# mega_meco.net
KiCad netlist of a schematic drawn in EAGLE
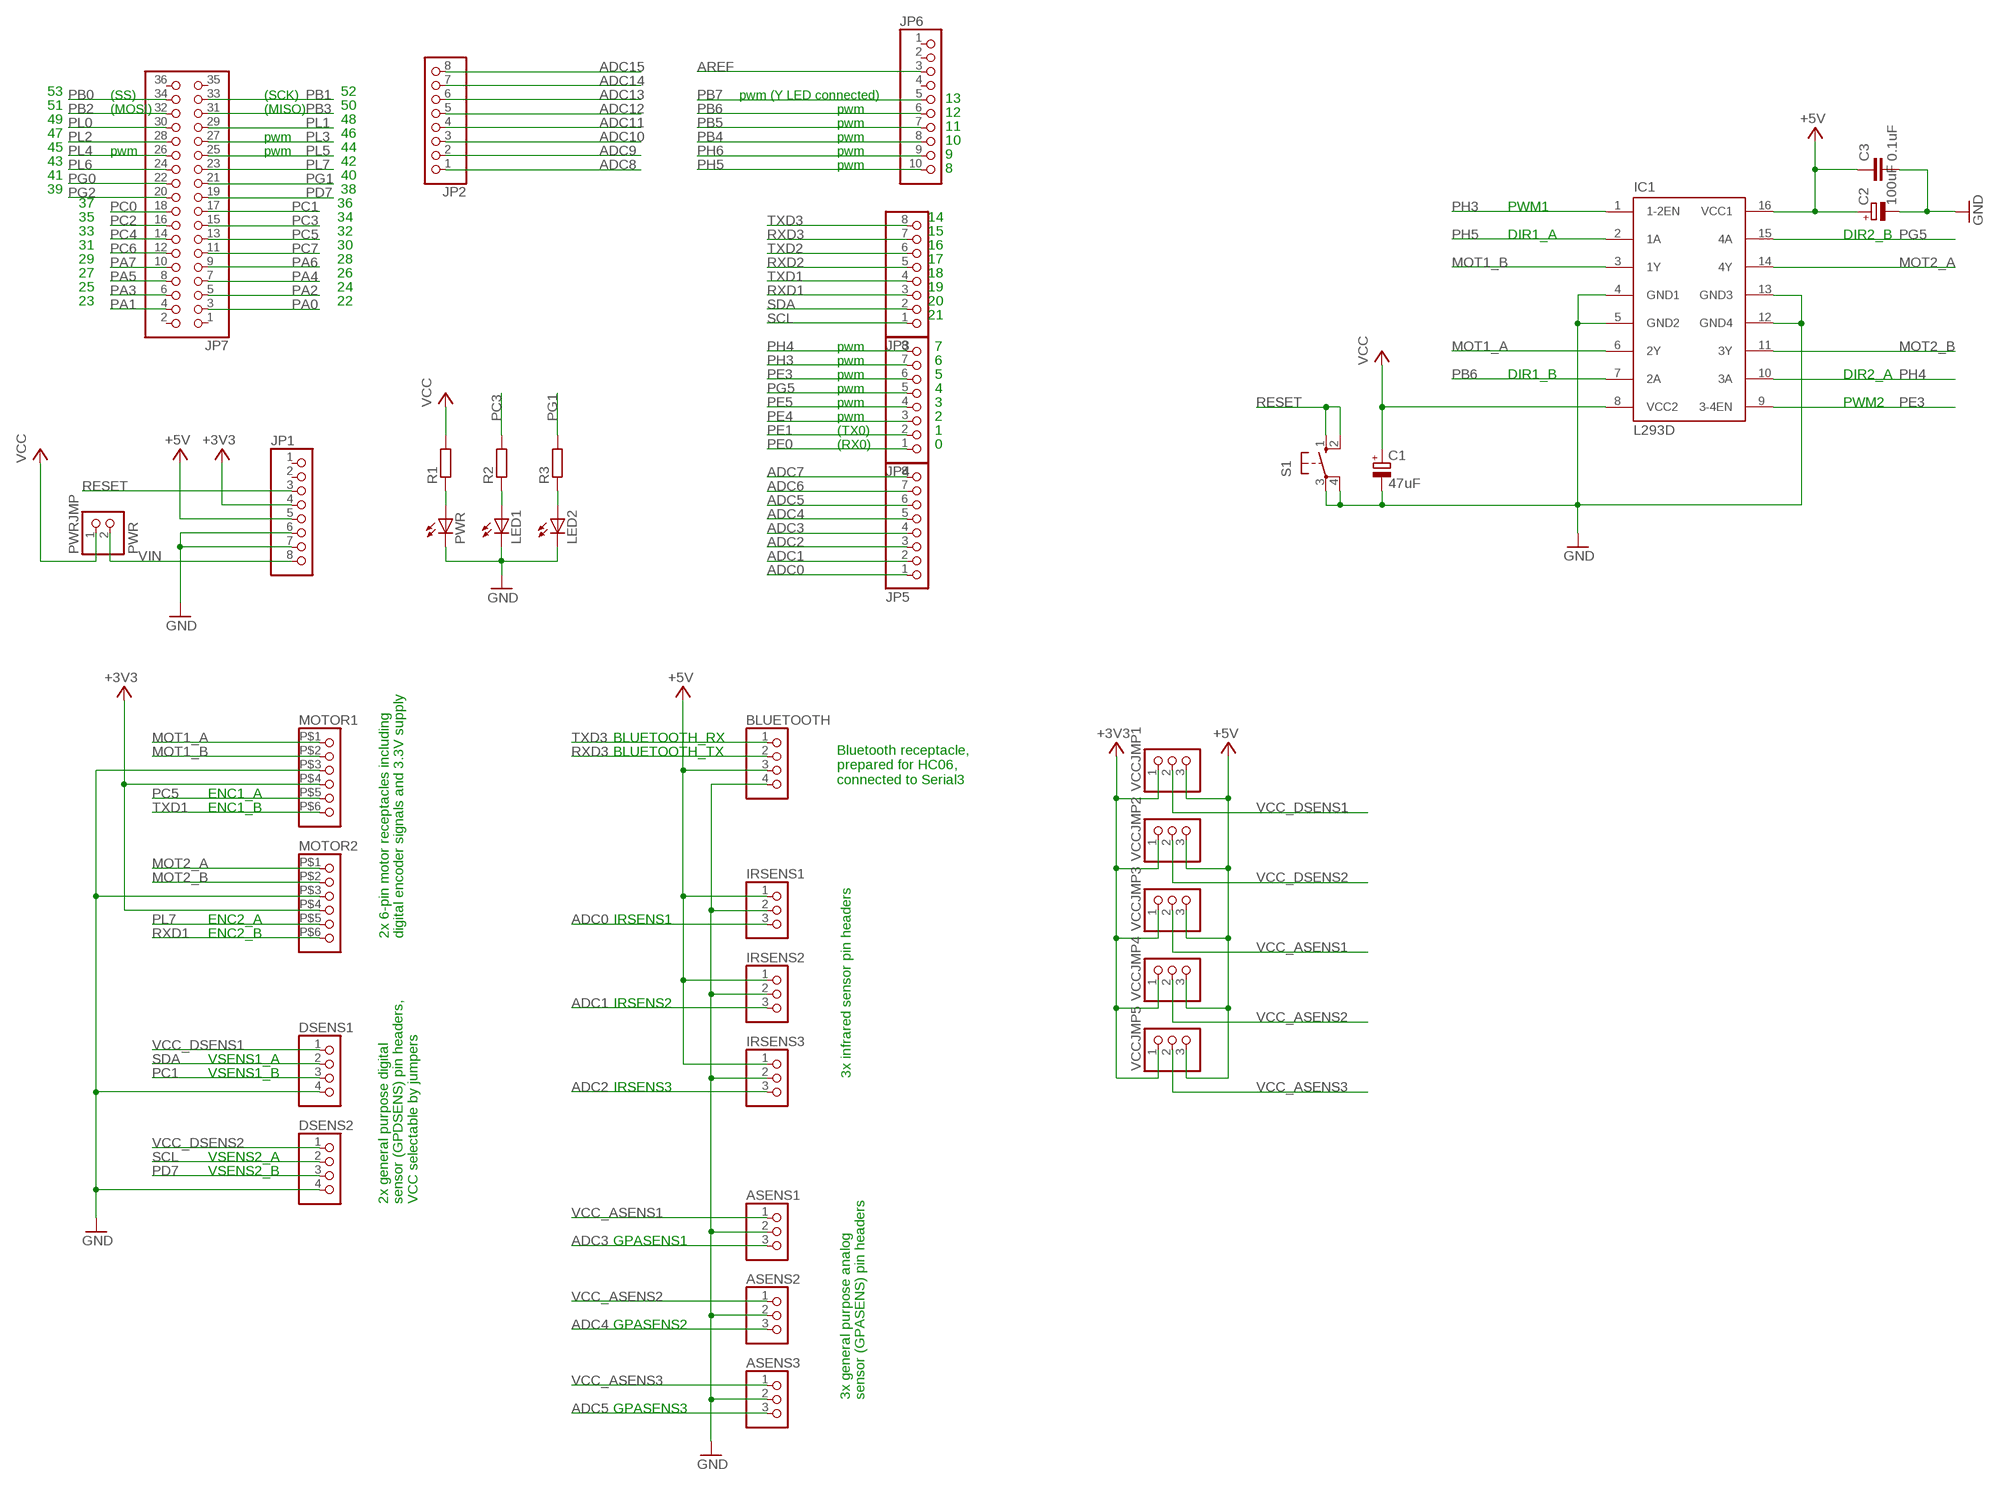
[diagram p0: schematic, sheet 1]

(export (version "E")
  (design (tool "Eeschema 10.0.6"))
  (components
    (comp (ref "ASENS1")
      (value "PINHD-1X3")
      (footprint "eagle-import:1X03")
      (libsource (lib "eagle-import") (part "PINHD-1X3"))
    )
    (comp (ref "ASENS2")
      (value "PINHD-1X3")
      (footprint "eagle-import:1X03")
      (libsource (lib "eagle-import") (part "PINHD-1X3"))
    )
    (comp (ref "ASENS3")
      (value "PINHD-1X3")
      (footprint "eagle-import:1X03")
      (libsource (lib "eagle-import") (part "PINHD-1X3"))
    )
    (comp (ref "BLUETOOTH")
      (value "PINHD-1X4")
      (footprint "eagle-import:1X04")
      (libsource (lib "eagle-import") (part "PINHD-1X4"))
    )
    (comp (ref "C1")
      (value "47uF")
      (footprint "eagle-import:E2-5")
      (libsource (lib "eagle-import") (part "CPOL-EUE2-5"))
    )
    (comp (ref "C2")
      (value "100uF")
      (footprint "eagle-import:E2-5")
      (libsource (lib "eagle-import") (part "CPOL-EUE2-5"))
    )
    (comp (ref "C3")
      (value "0.1uF")
      (footprint "eagle-import:C025-025X050")
      (libsource (lib "eagle-import") (part "C-EU025-025X050"))
    )
    (comp (ref "DSENS1")
      (value "PINHD-1X4")
      (footprint "eagle-import:1X04")
      (libsource (lib "eagle-import") (part "PINHD-1X4"))
    )
    (comp (ref "DSENS2")
      (value "PINHD-1X4")
      (footprint "eagle-import:1X04")
      (libsource (lib "eagle-import") (part "PINHD-1X4"))
    )
    (comp (ref "IC1")
      (value "L293D")
      (footprint "eagle-import:DIL16")
      (fields (field (name "MF") "Arrow Electronics") (field (name "MPN") "L293E"))
      (libsource (lib "eagle-import") (part "L293E"))
    )
    (comp (ref "IRSENS1")
      (value "PINHD-1X3")
      (footprint "eagle-import:1X03")
      (libsource (lib "eagle-import") (part "PINHD-1X3"))
    )
    (comp (ref "IRSENS2")
      (value "PINHD-1X3")
      (footprint "eagle-import:1X03")
      (libsource (lib "eagle-import") (part "PINHD-1X3"))
    )
    (comp (ref "IRSENS3")
      (value "PINHD-1X3")
      (footprint "eagle-import:1X03")
      (libsource (lib "eagle-import") (part "PINHD-1X3"))
    )
    (comp (ref "JP1")
      (value "PINHD-1X8")
      (footprint "eagle-import:1X08")
      (libsource (lib "eagle-import") (part "PINHD-1X8"))
    )
    (comp (ref "JP2")
      (value "PINHD-1X8")
      (footprint "eagle-import:1X08")
      (libsource (lib "eagle-import") (part "PINHD-1X8"))
    )
    (comp (ref "JP3")
      (value "PINHD-1X8")
      (footprint "eagle-import:1X08")
      (libsource (lib "eagle-import") (part "PINHD-1X8"))
    )
    (comp (ref "JP4")
      (value "PINHD-1X8")
      (footprint "eagle-import:1X08")
      (libsource (lib "eagle-import") (part "PINHD-1X8"))
    )
    (comp (ref "JP5")
      (value "PINHD-1X8")
      (footprint "eagle-import:1X08")
      (libsource (lib "eagle-import") (part "PINHD-1X8"))
    )
    (comp (ref "JP6")
      (value "PINHD-1X10")
      (footprint "eagle-import:1X10")
      (libsource (lib "eagle-import") (part "PINHD-1X10"))
    )
    (comp (ref "JP7")
      (value "PINHD-2X18")
      (footprint "eagle-import:2X18")
      (libsource (lib "eagle-import") (part "PINHD-2X18"))
    )
    (comp (ref "LED1")
      (value "LED3MM")
      (footprint "eagle-import:LED3MM")
      (libsource (lib "eagle-import") (part "LED3MM"))
    )
    (comp (ref "LED2")
      (value "LED3MM")
      (footprint "eagle-import:LED3MM")
      (libsource (lib "eagle-import") (part "LED3MM"))
    )
    (comp (ref "MOTOR1")
      (value "PINHD-1X6-2.5MM")
      (footprint "eagle-import:1X06-2.5MM")
      (libsource (lib "eagle-import") (part "PINHD-1X6-2.5MM"))
    )
    (comp (ref "MOTOR2")
      (value "PINHD-1X6-2.5MM")
      (footprint "eagle-import:1X06-2.5MM")
      (libsource (lib "eagle-import") (part "PINHD-1X6-2.5MM"))
    )
    (comp (ref "PWR")
      (value "LED5MM")
      (footprint "eagle-import:LED5MM")
      (libsource (lib "eagle-import") (part "LED5MM"))
    )
    (comp (ref "PWRJMP")
      (value "PWR")
      (footprint "eagle-import:1X02")
      (libsource (lib "eagle-import") (part "PINHD-1X2"))
    )
    (comp (ref "R1")
      (value "R-EU_0204/5")
      (footprint "eagle-import:0204_5")
      (libsource (lib "eagle-import") (part "R-EU_0204/5"))
    )
    (comp (ref "R2")
      (value "R-EU_0204/5")
      (footprint "eagle-import:0204_5")
      (libsource (lib "eagle-import") (part "R-EU_0204/5"))
    )
    (comp (ref "R3")
      (value "R-EU_0204/5")
      (footprint "eagle-import:0204_5")
      (libsource (lib "eagle-import") (part "R-EU_0204/5"))
    )
    (comp (ref "S1")
      (value "10-XX")
      (footprint "eagle-import:B3F-10XX")
      (fields (field (name "MPN") "B3F-1000"))
      (libsource (lib "eagle-import") (part "10-XX"))
    )
    (comp (ref "VCCJMP1")
      (value "PINHD-1X3")
      (footprint "eagle-import:1X03")
      (libsource (lib "eagle-import") (part "PINHD-1X3"))
    )
    (comp (ref "VCCJMP2")
      (value "PINHD-1X3")
      (footprint "eagle-import:1X03")
      (libsource (lib "eagle-import") (part "PINHD-1X3"))
    )
    (comp (ref "VCCJMP3")
      (value "PINHD-1X3")
      (footprint "eagle-import:1X03")
      (libsource (lib "eagle-import") (part "PINHD-1X3"))
    )
    (comp (ref "VCCJMP4")
      (value "PINHD-1X3")
      (footprint "eagle-import:1X03")
      (libsource (lib "eagle-import") (part "PINHD-1X3"))
    )
    (comp (ref "VCCJMP5")
      (value "PINHD-1X3")
      (footprint "eagle-import:1X03")
      (libsource (lib "eagle-import") (part "PINHD-1X3"))
    )
  )
  (nets
    (net (code "1") (name "+3V3") (class "Default")
      (node (ref "JP1") (pin "4") (pinfunction "4_4") (pintype "passive"))
      (node (ref "MOTOR1") (pin "P$4") (pinfunction "4_P$4") (pintype "passive"))
      (node (ref "MOTOR2") (pin "P$4") (pinfunction "4_P$4") (pintype "passive"))
      (node (ref "VCCJMP1") (pin "1") (pinfunction "1_1") (pintype "passive"))
      (node (ref "VCCJMP2") (pin "1") (pinfunction "1_1") (pintype "passive"))
      (node (ref "VCCJMP3") (pin "1") (pinfunction "1_1") (pintype "passive"))
      (node (ref "VCCJMP4") (pin "1") (pinfunction "1_1") (pintype "passive"))
      (node (ref "VCCJMP5") (pin "1") (pinfunction "1_1") (pintype "passive"))
    )
    (net (code "2") (name "+5V") (class "Default")
      (node (ref "BLUETOOTH") (pin "3") (pinfunction "3_3") (pintype "passive"))
      (node (ref "C2") (pin "+") (pinfunction "+_+") (pintype "passive"))
      (node (ref "C3") (pin "1") (pinfunction "1_1") (pintype "passive"))
      (node (ref "IC1") (pin "16") (pinfunction "VCC1_16") (pintype "power_in"))
      (node (ref "IRSENS1") (pin "1") (pinfunction "1_1") (pintype "passive"))
      (node (ref "IRSENS2") (pin "1") (pinfunction "1_1") (pintype "passive"))
      (node (ref "IRSENS3") (pin "1") (pinfunction "1_1") (pintype "passive"))
      (node (ref "JP1") (pin "5") (pinfunction "5_5") (pintype "passive"))
      (node (ref "VCCJMP1") (pin "3") (pinfunction "3_3") (pintype "passive"))
      (node (ref "VCCJMP2") (pin "3") (pinfunction "3_3") (pintype "passive"))
      (node (ref "VCCJMP3") (pin "3") (pinfunction "3_3") (pintype "passive"))
      (node (ref "VCCJMP4") (pin "3") (pinfunction "3_3") (pintype "passive"))
      (node (ref "VCCJMP5") (pin "3") (pinfunction "3_3") (pintype "passive"))
    )
    (net (code "3") (name "/ADC0") (class "Default")
      (node (ref "IRSENS1") (pin "3") (pinfunction "3_3") (pintype "passive"))
      (node (ref "JP5") (pin "1") (pinfunction "1_1") (pintype "passive"))
    )
    (net (code "4") (name "/ADC1") (class "Default")
      (node (ref "IRSENS2") (pin "3") (pinfunction "3_3") (pintype "passive"))
      (node (ref "JP5") (pin "2") (pinfunction "2_2") (pintype "passive"))
    )
    (net (code "5") (name "/ADC2") (class "Default")
      (node (ref "IRSENS3") (pin "3") (pinfunction "3_3") (pintype "passive"))
      (node (ref "JP5") (pin "3") (pinfunction "3_3") (pintype "passive"))
    )
    (net (code "6") (name "/ADC3") (class "Default")
      (node (ref "ASENS1") (pin "3") (pinfunction "3_3") (pintype "passive"))
      (node (ref "JP5") (pin "4") (pinfunction "4_4") (pintype "passive"))
    )
    (net (code "7") (name "/ADC4") (class "Default")
      (node (ref "ASENS2") (pin "3") (pinfunction "3_3") (pintype "passive"))
      (node (ref "JP5") (pin "5") (pinfunction "5_5") (pintype "passive"))
    )
    (net (code "8") (name "/ADC5") (class "Default")
      (node (ref "ASENS3") (pin "3") (pinfunction "3_3") (pintype "passive"))
      (node (ref "JP5") (pin "6") (pinfunction "6_6") (pintype "passive"))
    )
    (net (code "9") (name "/ADC6") (class "Default")
      (node (ref "JP5") (pin "7") (pinfunction "7_7") (pintype "passive"))
    )
    (net (code "10") (name "/ADC7") (class "Default")
      (node (ref "JP5") (pin "8") (pinfunction "8_8") (pintype "passive"))
    )
    (net (code "11") (name "/ADC8") (class "Default")
      (node (ref "JP2") (pin "1") (pinfunction "1_1") (pintype "passive"))
    )
    (net (code "12") (name "/ADC9") (class "Default")
      (node (ref "JP2") (pin "2") (pinfunction "2_2") (pintype "passive"))
    )
    (net (code "13") (name "/ADC10") (class "Default")
      (node (ref "JP2") (pin "3") (pinfunction "3_3") (pintype "passive"))
    )
    (net (code "14") (name "/ADC11") (class "Default")
      (node (ref "JP2") (pin "4") (pinfunction "4_4") (pintype "passive"))
    )
    (net (code "15") (name "/ADC12") (class "Default")
      (node (ref "JP2") (pin "5") (pinfunction "5_5") (pintype "passive"))
    )
    (net (code "16") (name "/ADC13") (class "Default")
      (node (ref "JP2") (pin "6") (pinfunction "6_6") (pintype "passive"))
    )
    (net (code "17") (name "/ADC14") (class "Default")
      (node (ref "JP2") (pin "7") (pinfunction "7_7") (pintype "passive"))
    )
    (net (code "18") (name "/ADC15") (class "Default")
      (node (ref "JP2") (pin "8") (pinfunction "8_8") (pintype "passive"))
    )
    (net (code "19") (name "/AREF") (class "Default")
      (node (ref "JP6") (pin "3") (pinfunction "3_3") (pintype "passive"))
    )
    (net (code "20") (name "/MOT1_A") (class "Default")
      (node (ref "IC1") (pin "6") (pinfunction "2Y_6") (pintype "output"))
      (node (ref "MOTOR1") (pin "P$1") (pinfunction "1_P$1") (pintype "passive"))
    )
    (net (code "21") (name "/MOT1_B") (class "Default")
      (node (ref "IC1") (pin "3") (pinfunction "1Y_3") (pintype "output"))
      (node (ref "MOTOR1") (pin "P$2") (pinfunction "2_P$2") (pintype "passive"))
    )
    (net (code "22") (name "/MOT2_A") (class "Default")
      (node (ref "IC1") (pin "14") (pinfunction "4Y_14") (pintype "output"))
      (node (ref "MOTOR2") (pin "P$1") (pinfunction "1_P$1") (pintype "passive"))
    )
    (net (code "23") (name "/MOT2_B") (class "Default")
      (node (ref "IC1") (pin "11") (pinfunction "3Y_11") (pintype "output"))
      (node (ref "MOTOR2") (pin "P$2") (pinfunction "2_P$2") (pintype "passive"))
    )
    (net (code "24") (name "/PA0") (class "Default")
      (node (ref "JP7") (pin "3") (pinfunction "3_3") (pintype "passive"))
    )
    (net (code "25") (name "/PA1") (class "Default")
      (node (ref "JP7") (pin "4") (pinfunction "4_4") (pintype "passive"))
    )
    (net (code "26") (name "/PA2") (class "Default")
      (node (ref "JP7") (pin "5") (pinfunction "5_5") (pintype "passive"))
    )
    (net (code "27") (name "/PA3") (class "Default")
      (node (ref "JP7") (pin "6") (pinfunction "6_6") (pintype "passive"))
    )
    (net (code "28") (name "/PA4") (class "Default")
      (node (ref "JP7") (pin "7") (pinfunction "7_7") (pintype "passive"))
    )
    (net (code "29") (name "/PA5") (class "Default")
      (node (ref "JP7") (pin "8") (pinfunction "8_8") (pintype "passive"))
    )
    (net (code "30") (name "/PA6") (class "Default")
      (node (ref "JP7") (pin "9") (pinfunction "9_9") (pintype "passive"))
    )
    (net (code "31") (name "/PA7") (class "Default")
      (node (ref "JP7") (pin "10") (pinfunction "10_10") (pintype "passive"))
    )
    (net (code "32") (name "/PB0") (class "Default")
      (node (ref "JP7") (pin "34") (pinfunction "34_34") (pintype "passive"))
    )
    (net (code "33") (name "/PB1") (class "Default")
      (node (ref "JP7") (pin "33") (pinfunction "33_33") (pintype "passive"))
    )
    (net (code "34") (name "/PB2") (class "Default")
      (node (ref "JP7") (pin "32") (pinfunction "32_32") (pintype "passive"))
    )
    (net (code "35") (name "/PB3") (class "Default")
      (node (ref "JP7") (pin "31") (pinfunction "31_31") (pintype "passive"))
    )
    (net (code "36") (name "/PB4") (class "Default")
      (node (ref "JP6") (pin "8") (pinfunction "8_8") (pintype "passive"))
    )
    (net (code "37") (name "/PB5") (class "Default")
      (node (ref "JP6") (pin "7") (pinfunction "7_7") (pintype "passive"))
    )
    (net (code "38") (name "/PB6") (class "Default")
      (node (ref "IC1") (pin "7") (pinfunction "2A_7") (pintype "input"))
      (node (ref "JP6") (pin "6") (pinfunction "6_6") (pintype "passive"))
    )
    (net (code "39") (name "/PB7") (class "Default")
      (node (ref "JP6") (pin "5") (pinfunction "5_5") (pintype "passive"))
    )
    (net (code "40") (name "/PC0") (class "Default")
      (node (ref "JP7") (pin "18") (pinfunction "18_18") (pintype "passive"))
    )
    (net (code "41") (name "/PC1") (class "Default")
      (node (ref "DSENS1") (pin "3") (pinfunction "3_3") (pintype "passive"))
      (node (ref "JP7") (pin "17") (pinfunction "17_17") (pintype "passive"))
    )
    (net (code "42") (name "/PC2") (class "Default")
      (node (ref "JP7") (pin "16") (pinfunction "16_16") (pintype "passive"))
    )
    (net (code "43") (name "/PC3") (class "Default")
      (node (ref "JP7") (pin "15") (pinfunction "15_15") (pintype "passive"))
      (node (ref "R2") (pin "2") (pinfunction "2_2") (pintype "passive"))
    )
    (net (code "44") (name "/PC4") (class "Default")
      (node (ref "JP7") (pin "14") (pinfunction "14_14") (pintype "passive"))
    )
    (net (code "45") (name "/PC5") (class "Default")
      (node (ref "JP7") (pin "13") (pinfunction "13_13") (pintype "passive"))
      (node (ref "MOTOR1") (pin "P$5") (pinfunction "5_P$5") (pintype "passive"))
    )
    (net (code "46") (name "/PC6") (class "Default")
      (node (ref "JP7") (pin "12") (pinfunction "12_12") (pintype "passive"))
    )
    (net (code "47") (name "/PC7") (class "Default")
      (node (ref "JP7") (pin "11") (pinfunction "11_11") (pintype "passive"))
    )
    (net (code "48") (name "/PD7") (class "Default")
      (node (ref "DSENS2") (pin "3") (pinfunction "3_3") (pintype "passive"))
      (node (ref "JP7") (pin "19") (pinfunction "19_19") (pintype "passive"))
    )
    (net (code "49") (name "/PE0") (class "Default")
      (node (ref "JP4") (pin "1") (pinfunction "1_1") (pintype "passive"))
    )
    (net (code "50") (name "/PE1") (class "Default")
      (node (ref "JP4") (pin "2") (pinfunction "2_2") (pintype "passive"))
    )
    (net (code "51") (name "/PE3") (class "Default")
      (node (ref "IC1") (pin "9") (pinfunction "3-4EN_9") (pintype "input"))
      (node (ref "JP4") (pin "6") (pinfunction "6_6") (pintype "passive"))
    )
    (net (code "52") (name "/PE4") (class "Default")
      (node (ref "JP4") (pin "3") (pinfunction "3_3") (pintype "passive"))
    )
    (net (code "53") (name "/PE5") (class "Default")
      (node (ref "JP4") (pin "4") (pinfunction "4_4") (pintype "passive"))
    )
    (net (code "54") (name "/PG0") (class "Default")
      (node (ref "JP7") (pin "22") (pinfunction "22_22") (pintype "passive"))
    )
    (net (code "55") (name "/PG1") (class "Default")
      (node (ref "JP7") (pin "21") (pinfunction "21_21") (pintype "passive"))
      (node (ref "R3") (pin "2") (pinfunction "2_2") (pintype "passive"))
    )
    (net (code "56") (name "/PG2") (class "Default")
      (node (ref "JP7") (pin "20") (pinfunction "20_20") (pintype "passive"))
    )
    (net (code "57") (name "/PG5") (class "Default")
      (node (ref "IC1") (pin "15") (pinfunction "4A_15") (pintype "input"))
      (node (ref "JP4") (pin "5") (pinfunction "5_5") (pintype "passive"))
    )
    (net (code "58") (name "/PH3") (class "Default")
      (node (ref "IC1") (pin "1") (pinfunction "1-2EN_1") (pintype "input"))
      (node (ref "JP4") (pin "7") (pinfunction "7_7") (pintype "passive"))
    )
    (net (code "59") (name "/PH4") (class "Default")
      (node (ref "IC1") (pin "10") (pinfunction "3A_10") (pintype "input"))
      (node (ref "JP4") (pin "8") (pinfunction "8_8") (pintype "passive"))
    )
    (net (code "60") (name "/PH5") (class "Default")
      (node (ref "IC1") (pin "2") (pinfunction "1A_2") (pintype "input"))
      (node (ref "JP6") (pin "10") (pinfunction "10_10") (pintype "passive"))
    )
    (net (code "61") (name "/PH6") (class "Default")
      (node (ref "JP6") (pin "9") (pinfunction "9_9") (pintype "passive"))
    )
    (net (code "62") (name "/PL0") (class "Default")
      (node (ref "JP7") (pin "30") (pinfunction "30_30") (pintype "passive"))
    )
    (net (code "63") (name "/PL1") (class "Default")
      (node (ref "JP7") (pin "29") (pinfunction "29_29") (pintype "passive"))
    )
    (net (code "64") (name "/PL2") (class "Default")
      (node (ref "JP7") (pin "28") (pinfunction "28_28") (pintype "passive"))
    )
    (net (code "65") (name "/PL3") (class "Default")
      (node (ref "JP7") (pin "27") (pinfunction "27_27") (pintype "passive"))
    )
    (net (code "66") (name "/PL4") (class "Default")
      (node (ref "JP7") (pin "26") (pinfunction "26_26") (pintype "passive"))
    )
    (net (code "67") (name "/PL5") (class "Default")
      (node (ref "JP7") (pin "25") (pinfunction "25_25") (pintype "passive"))
    )
    (net (code "68") (name "/PL6") (class "Default")
      (node (ref "JP7") (pin "24") (pinfunction "24_24") (pintype "passive"))
    )
    (net (code "69") (name "/PL7") (class "Default")
      (node (ref "JP7") (pin "23") (pinfunction "23_23") (pintype "passive"))
      (node (ref "MOTOR2") (pin "P$5") (pinfunction "5_P$5") (pintype "passive"))
    )
    (net (code "70") (name "/RESET") (class "Default")
      (node (ref "JP1") (pin "3") (pinfunction "3_3") (pintype "passive"))
      (node (ref "S1") (pin "1") (pinfunction "S_1") (pintype "passive"))
      (node (ref "S1") (pin "2") (pinfunction "S1_2") (pintype "passive"))
    )
    (net (code "71") (name "/RXD1") (class "Default")
      (node (ref "JP3") (pin "3") (pinfunction "3_3") (pintype "passive"))
      (node (ref "MOTOR2") (pin "P$6") (pinfunction "6_P$6") (pintype "passive"))
    )
    (net (code "72") (name "/RXD2") (class "Default")
      (node (ref "JP3") (pin "5") (pinfunction "5_5") (pintype "passive"))
    )
    (net (code "73") (name "/RXD3") (class "Default")
      (node (ref "BLUETOOTH") (pin "2") (pinfunction "2_2") (pintype "passive"))
      (node (ref "JP3") (pin "7") (pinfunction "7_7") (pintype "passive"))
    )
    (net (code "74") (name "/SCL") (class "Default")
      (node (ref "DSENS2") (pin "2") (pinfunction "2_2") (pintype "passive"))
      (node (ref "JP3") (pin "1") (pinfunction "1_1") (pintype "passive"))
    )
    (net (code "75") (name "/SDA") (class "Default")
      (node (ref "DSENS1") (pin "2") (pinfunction "2_2") (pintype "passive"))
      (node (ref "JP3") (pin "2") (pinfunction "2_2") (pintype "passive"))
    )
    (net (code "76") (name "/TXD1") (class "Default")
      (node (ref "JP3") (pin "4") (pinfunction "4_4") (pintype "passive"))
      (node (ref "MOTOR1") (pin "P$6") (pinfunction "6_P$6") (pintype "passive"))
    )
    (net (code "77") (name "/TXD2") (class "Default")
      (node (ref "JP3") (pin "6") (pinfunction "6_6") (pintype "passive"))
    )
    (net (code "78") (name "/TXD3") (class "Default")
      (node (ref "BLUETOOTH") (pin "1") (pinfunction "1_1") (pintype "passive"))
      (node (ref "JP3") (pin "8") (pinfunction "8_8") (pintype "passive"))
    )
    (net (code "79") (name "/VCC_ASENS1") (class "Default")
      (node (ref "ASENS1") (pin "1") (pinfunction "1_1") (pintype "passive"))
      (node (ref "VCCJMP3") (pin "2") (pinfunction "2_2") (pintype "passive"))
    )
    (net (code "80") (name "/VCC_ASENS2") (class "Default")
      (node (ref "ASENS2") (pin "1") (pinfunction "1_1") (pintype "passive"))
      (node (ref "VCCJMP4") (pin "2") (pinfunction "2_2") (pintype "passive"))
    )
    (net (code "81") (name "/VCC_ASENS3") (class "Default")
      (node (ref "ASENS3") (pin "1") (pinfunction "1_1") (pintype "passive"))
      (node (ref "VCCJMP5") (pin "2") (pinfunction "2_2") (pintype "passive"))
    )
    (net (code "82") (name "/VCC_DSENS1") (class "Default")
      (node (ref "DSENS1") (pin "1") (pinfunction "1_1") (pintype "passive"))
      (node (ref "VCCJMP1") (pin "2") (pinfunction "2_2") (pintype "passive"))
    )
    (net (code "83") (name "/VCC_DSENS2") (class "Default")
      (node (ref "DSENS2") (pin "1") (pinfunction "1_1") (pintype "passive"))
      (node (ref "VCCJMP2") (pin "2") (pinfunction "2_2") (pintype "passive"))
    )
    (net (code "84") (name "/VIN") (class "Default")
      (node (ref "JP1") (pin "8") (pinfunction "8_8") (pintype "passive"))
      (node (ref "PWRJMP") (pin "2") (pinfunction "2_2") (pintype "passive"))
    )
    (net (code "85") (name "GND") (class "Default")
      (node (ref "ASENS1") (pin "2") (pinfunction "2_2") (pintype "passive"))
      (node (ref "ASENS2") (pin "2") (pinfunction "2_2") (pintype "passive"))
      (node (ref "ASENS3") (pin "2") (pinfunction "2_2") (pintype "passive"))
      (node (ref "BLUETOOTH") (pin "4") (pinfunction "4_4") (pintype "passive"))
      (node (ref "C1") (pin "-") (pinfunction "-_-") (pintype "passive"))
      (node (ref "C2") (pin "-") (pinfunction "-_-") (pintype "passive"))
      (node (ref "C3") (pin "2") (pinfunction "2_2") (pintype "passive"))
      (node (ref "DSENS1") (pin "4") (pinfunction "4_4") (pintype "passive"))
      (node (ref "DSENS2") (pin "4") (pinfunction "4_4") (pintype "passive"))
      (node (ref "IC1") (pin "12") (pinfunction "GND4_12") (pintype "power_in"))
      (node (ref "IC1") (pin "13") (pinfunction "GND3_13") (pintype "power_in"))
      (node (ref "IC1") (pin "4") (pinfunction "GND1_4") (pintype "power_in"))
      (node (ref "IC1") (pin "5") (pinfunction "GND2_5") (pintype "power_in"))
      (node (ref "IRSENS1") (pin "2") (pinfunction "2_2") (pintype "passive"))
      (node (ref "IRSENS2") (pin "2") (pinfunction "2_2") (pintype "passive"))
      (node (ref "IRSENS3") (pin "2") (pinfunction "2_2") (pintype "passive"))
      (node (ref "JP1") (pin "6") (pinfunction "6_6") (pintype "passive"))
      (node (ref "JP1") (pin "7") (pinfunction "7_7") (pintype "passive"))
      (node (ref "LED1") (pin "K") (pinfunction "C_K") (pintype "passive"))
      (node (ref "LED2") (pin "K") (pinfunction "C_K") (pintype "passive"))
      (node (ref "MOTOR1") (pin "P$3") (pinfunction "3_P$3") (pintype "passive"))
      (node (ref "MOTOR2") (pin "P$3") (pinfunction "3_P$3") (pintype "passive"))
      (node (ref "PWR") (pin "K") (pinfunction "C_K") (pintype "passive"))
      (node (ref "S1") (pin "3") (pinfunction "P_3") (pintype "passive"))
      (node (ref "S1") (pin "4") (pinfunction "P1_4") (pintype "passive"))
    )
    (net (code "86") (name "Net-(LED1-PadA)") (class "Default")
      (node (ref "LED1") (pin "A") (pinfunction "A_A") (pintype "passive"))
      (node (ref "R2") (pin "1") (pinfunction "1_1") (pintype "passive"))
    )
    (net (code "87") (name "Net-(LED2-PadA)") (class "Default")
      (node (ref "LED2") (pin "A") (pinfunction "A_A") (pintype "passive"))
      (node (ref "R3") (pin "1") (pinfunction "1_1") (pintype "passive"))
    )
    (net (code "88") (name "Net-(PWR-PadA)") (class "Default")
      (node (ref "PWR") (pin "A") (pinfunction "A_A") (pintype "passive"))
      (node (ref "R1") (pin "1") (pinfunction "1_1") (pintype "passive"))
    )
    (net (code "89") (name "VCC") (class "Default")
      (node (ref "C1") (pin "+") (pinfunction "+_+") (pintype "passive"))
      (node (ref "IC1") (pin "8") (pinfunction "VCC2_8") (pintype "power_in"))
      (node (ref "PWRJMP") (pin "1") (pinfunction "1_1") (pintype "passive"))
      (node (ref "R1") (pin "2") (pinfunction "2_2") (pintype "passive"))
    )
    (net (code "90") (name "unconnected-(JP1-Pad1)") (class "Default")
      (node (ref "JP1") (pin "1") (pinfunction "1_1") (pintype "passive"))
    )
    (net (code "91") (name "unconnected-(JP1-Pad2)") (class "Default")
      (node (ref "JP1") (pin "2") (pinfunction "2_2") (pintype "passive"))
    )
    (net (code "92") (name "unconnected-(JP6-Pad1)") (class "Default")
      (node (ref "JP6") (pin "1") (pinfunction "1_1") (pintype "passive"))
    )
    (net (code "93") (name "unconnected-(JP6-Pad2)") (class "Default")
      (node (ref "JP6") (pin "2") (pinfunction "2_2") (pintype "passive"))
    )
    (net (code "94") (name "unconnected-(JP6-Pad4)") (class "Default")
      (node (ref "JP6") (pin "4") (pinfunction "4_4") (pintype "passive"))
    )
    (net (code "95") (name "unconnected-(JP7-Pad1)") (class "Default")
      (node (ref "JP7") (pin "1") (pinfunction "1_1") (pintype "passive"))
    )
    (net (code "96") (name "unconnected-(JP7-Pad2)") (class "Default")
      (node (ref "JP7") (pin "2") (pinfunction "2_2") (pintype "passive"))
    )
    (net (code "97") (name "unconnected-(JP7-Pad35)") (class "Default")
      (node (ref "JP7") (pin "35") (pinfunction "35_35") (pintype "passive"))
    )
    (net (code "98") (name "unconnected-(JP7-Pad36)") (class "Default")
      (node (ref "JP7") (pin "36") (pinfunction "36_36") (pintype "passive"))
    )
  )
)
